# Syno_Ver1_0.net
KiCad netlist of a schematic drawn in EAGLE
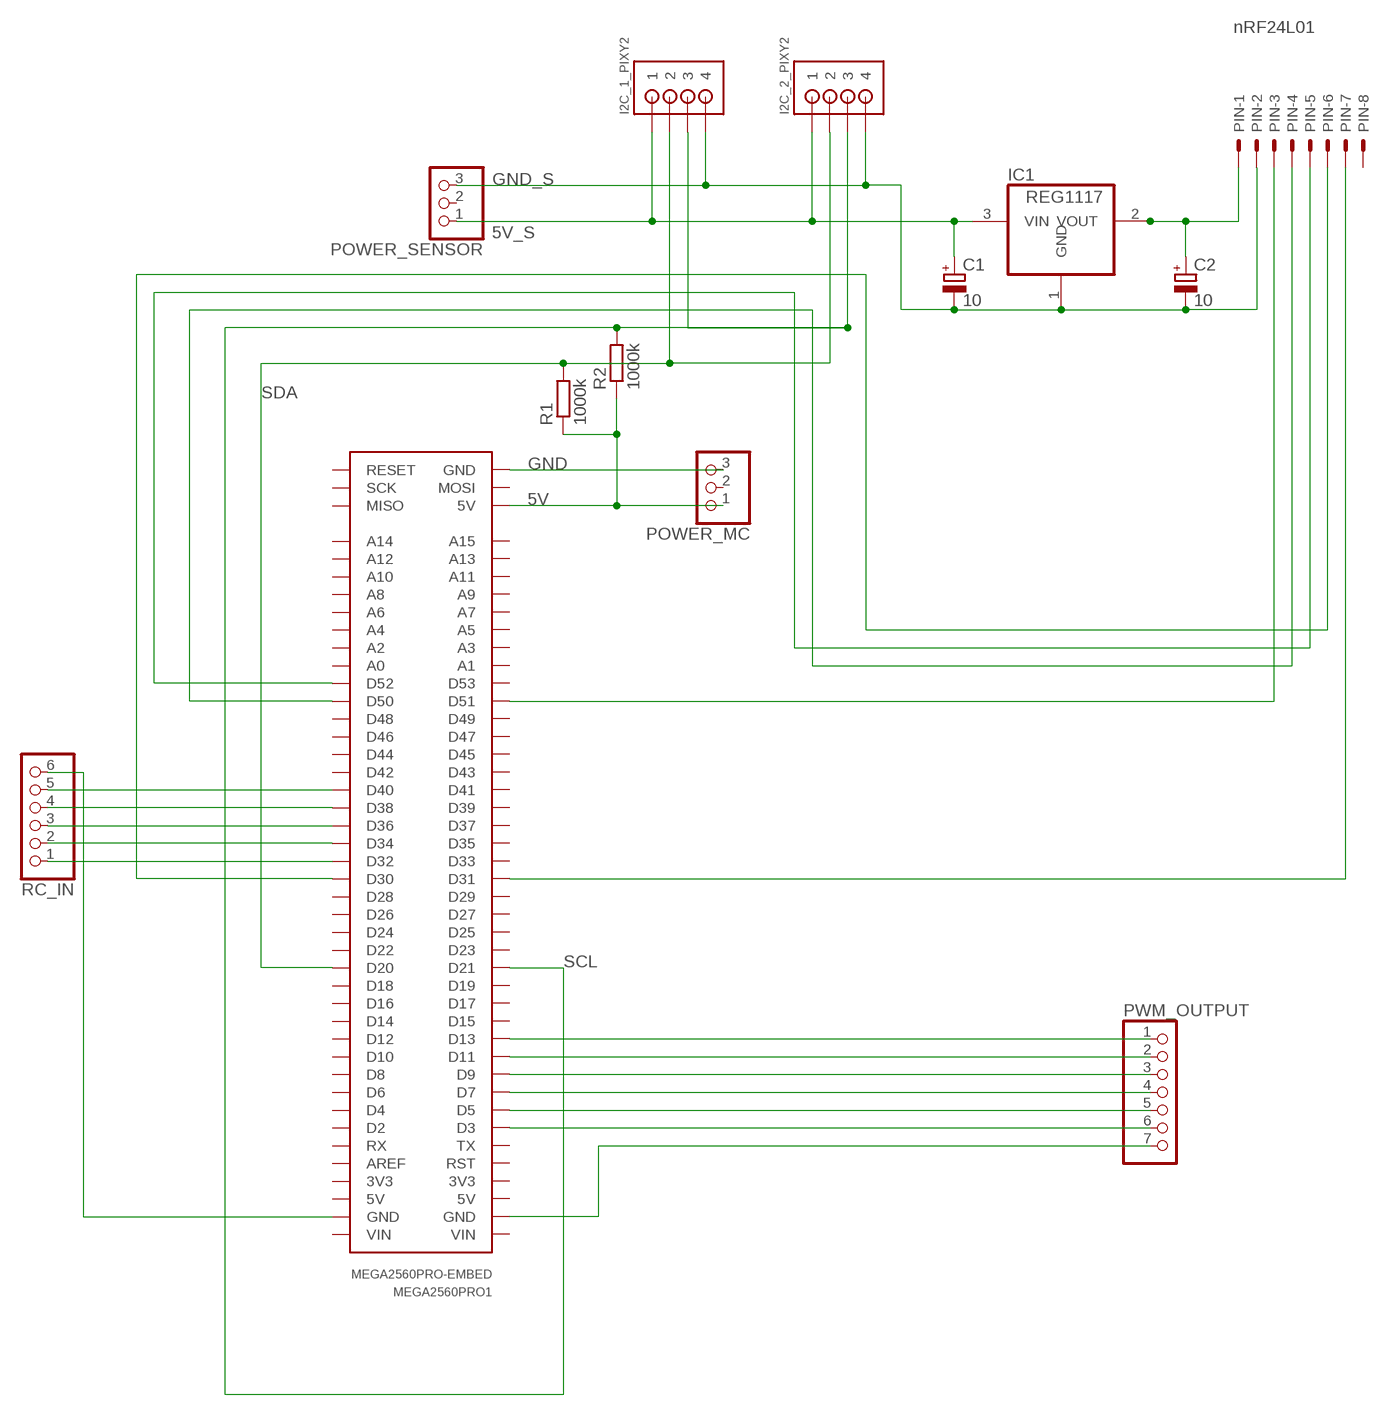
[diagram p0: schematic, sheet 1]

(export (version "E")
  (design (tool "Eeschema 10.0.6"))
  (components
    (comp (ref "C1")
      (value "10")
      (footprint "eagle-import:E1,8-4")
      (libsource (lib "eagle-import") (part "CPOL-EUE1.8-4"))
    )
    (comp (ref "C2")
      (value "10")
      (footprint "eagle-import:E1,8-4")
      (libsource (lib "eagle-import") (part "CPOL-EUE1.8-4"))
    )
    (comp (ref "I2C_1_PIXY2")
      (value "JST-PH_4-PIN_HEADER")
      (footprint "eagle-import:JST_B4B-PH_HEADER")
      (libsource (lib "eagle-import") (part "JST-PH_4-PIN_HEADER"))
    )
    (comp (ref "I2C_2_PIXY2")
      (value "JST-PH_4-PIN_HEADER")
      (footprint "eagle-import:JST_B4B-PH_HEADER")
      (libsource (lib "eagle-import") (part "JST-PH_4-PIN_HEADER"))
    )
    (comp (ref "IC1")
      (value "REG1117")
      (footprint "eagle-import:SOT223")
      (libsource (lib "eagle-import") (part "REG1117"))
    )
    (comp (ref "MEGA2560PRO1")
      (value "MEGA2560PRO-EMBED")
      (footprint "eagle-import:MEGA2560PRO-EMBED")
      (libsource (lib "eagle-import") (part "MEGA2560PRO-EMBED"))
    )
    (comp (ref "PIN")
      (value "nRF24L01")
      (footprint "eagle-import:JST-XH-08-PACKAGE-ROUND-PAD")
      (libsource (lib "eagle-import") (part "JST-XH-08-PIN-ROUND-PAD"))
    )
    (comp (ref "POWER_MC")
      (value "PINHD-1X3/90")
      (footprint "eagle-import:1X03_90")
      (libsource (lib "eagle-import") (part "PINHD-1X3/90"))
    )
    (comp (ref "POWER_SENSOR")
      (value "PINHD-1X3/90")
      (footprint "eagle-import:1X03_90")
      (libsource (lib "eagle-import") (part "PINHD-1X3/90"))
    )
    (comp (ref "PWM_OUTPUT")
      (value "PINHD-1X7/90")
      (footprint "eagle-import:1X07_90")
      (libsource (lib "eagle-import") (part "PINHD-1X7/90"))
    )
    (comp (ref "R1")
      (value "1000k")
      (footprint "eagle-import:0204_5")
      (libsource (lib "eagle-import") (part "R-EU_0204/5"))
    )
    (comp (ref "R2")
      (value "1000k")
      (footprint "eagle-import:0204_5")
      (libsource (lib "eagle-import") (part "R-EU_0204/5"))
    )
    (comp (ref "RC_IN")
      (value "PINHD-1X6/90")
      (footprint "eagle-import:1X06_90")
      (libsource (lib "eagle-import") (part "PINHD-1X6/90"))
    )
  )
  (nets
    (net (code "1") (name "/5V") (class "Default")
      (node (ref "MEGA2560PRO1") (pin "5V@3") (pinfunction "5V_5V@3") (pintype "bidirectional"))
      (node (ref "POWER_MC") (pin "1") (pinfunction "1_1") (pintype "passive"))
      (node (ref "R1") (pin "1") (pinfunction "1_1") (pintype "passive"))
      (node (ref "R2") (pin "1") (pinfunction "1_1") (pintype "passive"))
    )
    (net (code "2") (name "/5V_S") (class "Default")
      (node (ref "C1") (pin "+") (pinfunction "+_+") (pintype "passive"))
      (node (ref "I2C_1_PIXY2") (pin "P1") (pinfunction "1_P1") (pintype "bidirectional"))
      (node (ref "I2C_2_PIXY2") (pin "P1") (pinfunction "1_P1") (pintype "bidirectional"))
      (node (ref "IC1") (pin "3") (pinfunction "VIN_3") (pintype "input"))
      (node (ref "POWER_SENSOR") (pin "1") (pinfunction "1_1") (pintype "passive"))
    )
    (net (code "3") (name "/GND") (class "Default")
      (node (ref "MEGA2560PRO1") (pin "GND@3") (pinfunction "GND_GND@3") (pintype "bidirectional"))
      (node (ref "POWER_MC") (pin "3") (pinfunction "3_3") (pintype "passive"))
    )
    (net (code "4") (name "/GND_S") (class "Default")
      (node (ref "C1") (pin "-") (pinfunction "-_-") (pintype "passive"))
      (node (ref "C2") (pin "-") (pinfunction "-_-") (pintype "passive"))
      (node (ref "I2C_1_PIXY2") (pin "P4") (pinfunction "4_P4") (pintype "bidirectional"))
      (node (ref "I2C_2_PIXY2") (pin "P4") (pinfunction "4_P4") (pintype "bidirectional"))
      (node (ref "IC1") (pin "1") (pinfunction "GND_1") (pintype "power_in"))
      (node (ref "PIN") (pin "2") (pinfunction "S_2") (pintype "passive"))
      (node (ref "POWER_SENSOR") (pin "3") (pinfunction "3_3") (pintype "passive"))
    )
    (net (code "5") (name "/SCL") (class "Default")
      (node (ref "I2C_1_PIXY2") (pin "P3") (pinfunction "3_P3") (pintype "bidirectional"))
      (node (ref "I2C_2_PIXY2") (pin "P3") (pinfunction "3_P3") (pintype "bidirectional"))
      (node (ref "MEGA2560PRO1") (pin "D21") (pinfunction "D21_D21") (pintype "bidirectional"))
      (node (ref "R2") (pin "2") (pinfunction "2_2") (pintype "passive"))
    )
    (net (code "6") (name "/SDA") (class "Default")
      (node (ref "I2C_1_PIXY2") (pin "P2") (pinfunction "2_P2") (pintype "bidirectional"))
      (node (ref "I2C_2_PIXY2") (pin "P2") (pinfunction "2_P2") (pintype "bidirectional"))
      (node (ref "MEGA2560PRO1") (pin "D20") (pinfunction "D20_D20") (pintype "bidirectional"))
      (node (ref "R1") (pin "2") (pinfunction "2_2") (pintype "passive"))
    )
    (net (code "7") (name "Net-(IC1-VOUT)") (class "Default")
      (node (ref "C2") (pin "+") (pinfunction "+_+") (pintype "passive"))
      (node (ref "IC1") (pin "2") (pinfunction "VOUT_2") (pintype "output"))
      (node (ref "PIN") (pin "1") (pinfunction "S_1") (pintype "passive"))
    )
    (net (code "8") (name "Net-(MEGA2560PRO1-GND-PadGND@1)") (class "Default")
      (node (ref "MEGA2560PRO1") (pin "GND@1") (pinfunction "GND_GND@1") (pintype "bidirectional"))
      (node (ref "PWM_OUTPUT") (pin "7") (pinfunction "7_7") (pintype "passive"))
    )
    (net (code "9") (name "Net-(MEGA2560PRO1-GND-PadGND@2)") (class "Default")
      (node (ref "MEGA2560PRO1") (pin "GND@2") (pinfunction "GND_GND@2") (pintype "bidirectional"))
      (node (ref "RC_IN") (pin "6") (pinfunction "6_6") (pintype "passive"))
    )
    (net (code "10") (name "Net-(MEGA2560PRO1-PadD3)") (class "Default")
      (node (ref "MEGA2560PRO1") (pin "D3") (pinfunction "D3_D3") (pintype "bidirectional"))
      (node (ref "PWM_OUTPUT") (pin "6") (pinfunction "6_6") (pintype "passive"))
    )
    (net (code "11") (name "Net-(MEGA2560PRO1-PadD5)") (class "Default")
      (node (ref "MEGA2560PRO1") (pin "D5") (pinfunction "D5_D5") (pintype "bidirectional"))
      (node (ref "PWM_OUTPUT") (pin "5") (pinfunction "5_5") (pintype "passive"))
    )
    (net (code "12") (name "Net-(MEGA2560PRO1-PadD7)") (class "Default")
      (node (ref "MEGA2560PRO1") (pin "D7") (pinfunction "D7_D7") (pintype "bidirectional"))
      (node (ref "PWM_OUTPUT") (pin "4") (pinfunction "4_4") (pintype "passive"))
    )
    (net (code "13") (name "Net-(MEGA2560PRO1-PadD9)") (class "Default")
      (node (ref "MEGA2560PRO1") (pin "D9") (pinfunction "D9_D9") (pintype "bidirectional"))
      (node (ref "PWM_OUTPUT") (pin "3") (pinfunction "3_3") (pintype "passive"))
    )
    (net (code "14") (name "Net-(MEGA2560PRO1-PadD11)") (class "Default")
      (node (ref "MEGA2560PRO1") (pin "D11") (pinfunction "D11_D11") (pintype "bidirectional"))
      (node (ref "PWM_OUTPUT") (pin "2") (pinfunction "2_2") (pintype "passive"))
    )
    (net (code "15") (name "Net-(MEGA2560PRO1-PadD13)") (class "Default")
      (node (ref "MEGA2560PRO1") (pin "D13") (pinfunction "D13_D13") (pintype "bidirectional"))
      (node (ref "PWM_OUTPUT") (pin "1") (pinfunction "1_1") (pintype "passive"))
    )
    (net (code "16") (name "Net-(MEGA2560PRO1-PadD32)") (class "Default")
      (node (ref "MEGA2560PRO1") (pin "D32") (pinfunction "D32_D32") (pintype "bidirectional"))
      (node (ref "RC_IN") (pin "1") (pinfunction "1_1") (pintype "passive"))
    )
    (net (code "17") (name "Net-(MEGA2560PRO1-PadD34)") (class "Default")
      (node (ref "MEGA2560PRO1") (pin "D34") (pinfunction "D34_D34") (pintype "bidirectional"))
      (node (ref "RC_IN") (pin "2") (pinfunction "2_2") (pintype "passive"))
    )
    (net (code "18") (name "Net-(MEGA2560PRO1-PadD36)") (class "Default")
      (node (ref "MEGA2560PRO1") (pin "D36") (pinfunction "D36_D36") (pintype "bidirectional"))
      (node (ref "RC_IN") (pin "3") (pinfunction "3_3") (pintype "passive"))
    )
    (net (code "19") (name "Net-(MEGA2560PRO1-PadD38)") (class "Default")
      (node (ref "MEGA2560PRO1") (pin "D38") (pinfunction "D38_D38") (pintype "bidirectional"))
      (node (ref "RC_IN") (pin "4") (pinfunction "4_4") (pintype "passive"))
    )
    (net (code "20") (name "Net-(MEGA2560PRO1-PadD40)") (class "Default")
      (node (ref "MEGA2560PRO1") (pin "D40") (pinfunction "D40_D40") (pintype "bidirectional"))
      (node (ref "RC_IN") (pin "5") (pinfunction "5_5") (pintype "passive"))
    )
    (net (code "21") (name "Net-(PINC-S)") (class "Default")
      (node (ref "MEGA2560PRO1") (pin "D51") (pinfunction "D51_D51") (pintype "bidirectional"))
      (node (ref "PIN") (pin "3") (pinfunction "S_3") (pintype "passive"))
    )
    (net (code "22") (name "Net-(PIND-S)") (class "Default")
      (node (ref "MEGA2560PRO1") (pin "D50") (pinfunction "D50_D50") (pintype "bidirectional"))
      (node (ref "PIN") (pin "4") (pinfunction "S_4") (pintype "passive"))
    )
    (net (code "23") (name "Net-(PINE-S)") (class "Default")
      (node (ref "MEGA2560PRO1") (pin "D52") (pinfunction "D52_D52") (pintype "bidirectional"))
      (node (ref "PIN") (pin "5") (pinfunction "S_5") (pintype "passive"))
    )
    (net (code "24") (name "Net-(PINF-S)") (class "Default")
      (node (ref "MEGA2560PRO1") (pin "D30") (pinfunction "D30_D30") (pintype "bidirectional"))
      (node (ref "PIN") (pin "6") (pinfunction "S_6") (pintype "passive"))
    )
    (net (code "25") (name "Net-(PING-S)") (class "Default")
      (node (ref "MEGA2560PRO1") (pin "D31") (pinfunction "D31_D31") (pintype "bidirectional"))
      (node (ref "PIN") (pin "7") (pinfunction "S_7") (pintype "passive"))
    )
    (net (code "26") (name "unconnected-(MEGA2560PRO1-3V3-Pad3V3@1)") (class "Default")
      (node (ref "MEGA2560PRO1") (pin "3V3@1") (pinfunction "3V3_3V3@1") (pintype "bidirectional"))
    )
    (net (code "27") (name "unconnected-(MEGA2560PRO1-3V3-Pad3V3@2)") (class "Default")
      (node (ref "MEGA2560PRO1") (pin "3V3@2") (pinfunction "3V3_3V3@2") (pintype "bidirectional"))
    )
    (net (code "28") (name "unconnected-(MEGA2560PRO1-5V-Pad5V@1)") (class "Default")
      (node (ref "MEGA2560PRO1") (pin "5V@1") (pinfunction "5V_5V@1") (pintype "bidirectional"))
    )
    (net (code "29") (name "unconnected-(MEGA2560PRO1-5V-Pad5V@2)") (class "Default")
      (node (ref "MEGA2560PRO1") (pin "5V@2") (pinfunction "5V_5V@2") (pintype "bidirectional"))
    )
    (net (code "30") (name "unconnected-(MEGA2560PRO1-PadA0)") (class "Default")
      (node (ref "MEGA2560PRO1") (pin "A0") (pinfunction "A0_A0") (pintype "bidirectional"))
    )
    (net (code "31") (name "unconnected-(MEGA2560PRO1-PadA1)") (class "Default")
      (node (ref "MEGA2560PRO1") (pin "A1") (pinfunction "A1_A1") (pintype "bidirectional"))
    )
    (net (code "32") (name "unconnected-(MEGA2560PRO1-PadA2)") (class "Default")
      (node (ref "MEGA2560PRO1") (pin "A2") (pinfunction "A2_A2") (pintype "bidirectional"))
    )
    (net (code "33") (name "unconnected-(MEGA2560PRO1-PadA3)") (class "Default")
      (node (ref "MEGA2560PRO1") (pin "A3") (pinfunction "A3_A3") (pintype "bidirectional"))
    )
    (net (code "34") (name "unconnected-(MEGA2560PRO1-PadA4)") (class "Default")
      (node (ref "MEGA2560PRO1") (pin "A4") (pinfunction "A4_A4") (pintype "bidirectional"))
    )
    (net (code "35") (name "unconnected-(MEGA2560PRO1-PadA5)") (class "Default")
      (node (ref "MEGA2560PRO1") (pin "A5") (pinfunction "A5_A5") (pintype "bidirectional"))
    )
    (net (code "36") (name "unconnected-(MEGA2560PRO1-PadA6)") (class "Default")
      (node (ref "MEGA2560PRO1") (pin "A6") (pinfunction "A6_A6") (pintype "bidirectional"))
    )
    (net (code "37") (name "unconnected-(MEGA2560PRO1-PadA7)") (class "Default")
      (node (ref "MEGA2560PRO1") (pin "A7") (pinfunction "A7_A7") (pintype "bidirectional"))
    )
    (net (code "38") (name "unconnected-(MEGA2560PRO1-PadA8)") (class "Default")
      (node (ref "MEGA2560PRO1") (pin "A8") (pinfunction "A8_A8") (pintype "bidirectional"))
    )
    (net (code "39") (name "unconnected-(MEGA2560PRO1-PadA9)") (class "Default")
      (node (ref "MEGA2560PRO1") (pin "A9") (pinfunction "A9_A9") (pintype "bidirectional"))
    )
    (net (code "40") (name "unconnected-(MEGA2560PRO1-PadA10)") (class "Default")
      (node (ref "MEGA2560PRO1") (pin "A10") (pinfunction "A10_A10") (pintype "bidirectional"))
    )
    (net (code "41") (name "unconnected-(MEGA2560PRO1-PadA11)") (class "Default")
      (node (ref "MEGA2560PRO1") (pin "A11") (pinfunction "A11_A11") (pintype "bidirectional"))
    )
    (net (code "42") (name "unconnected-(MEGA2560PRO1-PadA12)") (class "Default")
      (node (ref "MEGA2560PRO1") (pin "A12") (pinfunction "A12_A12") (pintype "bidirectional"))
    )
    (net (code "43") (name "unconnected-(MEGA2560PRO1-PadA13)") (class "Default")
      (node (ref "MEGA2560PRO1") (pin "A13") (pinfunction "A13_A13") (pintype "bidirectional"))
    )
    (net (code "44") (name "unconnected-(MEGA2560PRO1-PadA14)") (class "Default")
      (node (ref "MEGA2560PRO1") (pin "A14") (pinfunction "A14_A14") (pintype "bidirectional"))
    )
    (net (code "45") (name "unconnected-(MEGA2560PRO1-PadA15)") (class "Default")
      (node (ref "MEGA2560PRO1") (pin "A15") (pinfunction "A15_A15") (pintype "bidirectional"))
    )
    (net (code "46") (name "unconnected-(MEGA2560PRO1-PadAREF)") (class "Default")
      (node (ref "MEGA2560PRO1") (pin "AREF") (pinfunction "AREF_AREF") (pintype "bidirectional"))
    )
    (net (code "47") (name "unconnected-(MEGA2560PRO1-PadD2)") (class "Default")
      (node (ref "MEGA2560PRO1") (pin "D2") (pinfunction "D2_D2") (pintype "bidirectional"))
    )
    (net (code "48") (name "unconnected-(MEGA2560PRO1-PadD4)") (class "Default")
      (node (ref "MEGA2560PRO1") (pin "D4") (pinfunction "D4_D4") (pintype "bidirectional"))
    )
    (net (code "49") (name "unconnected-(MEGA2560PRO1-PadD6)") (class "Default")
      (node (ref "MEGA2560PRO1") (pin "D6") (pinfunction "D6_D6") (pintype "bidirectional"))
    )
    (net (code "50") (name "unconnected-(MEGA2560PRO1-PadD8)") (class "Default")
      (node (ref "MEGA2560PRO1") (pin "D8") (pinfunction "D8_D8") (pintype "bidirectional"))
    )
    (net (code "51") (name "unconnected-(MEGA2560PRO1-PadD10)") (class "Default")
      (node (ref "MEGA2560PRO1") (pin "D10") (pinfunction "D10_D10") (pintype "bidirectional"))
    )
    (net (code "52") (name "unconnected-(MEGA2560PRO1-PadD12)") (class "Default")
      (node (ref "MEGA2560PRO1") (pin "D12") (pinfunction "D12_D12") (pintype "bidirectional"))
    )
    (net (code "53") (name "unconnected-(MEGA2560PRO1-PadD14)") (class "Default")
      (node (ref "MEGA2560PRO1") (pin "D14") (pinfunction "D14_D14") (pintype "bidirectional"))
    )
    (net (code "54") (name "unconnected-(MEGA2560PRO1-PadD15)") (class "Default")
      (node (ref "MEGA2560PRO1") (pin "D15") (pinfunction "D15_D15") (pintype "bidirectional"))
    )
    (net (code "55") (name "unconnected-(MEGA2560PRO1-PadD16)") (class "Default")
      (node (ref "MEGA2560PRO1") (pin "D16") (pinfunction "D16_D16") (pintype "bidirectional"))
    )
    (net (code "56") (name "unconnected-(MEGA2560PRO1-PadD17)") (class "Default")
      (node (ref "MEGA2560PRO1") (pin "D17") (pinfunction "D17_D17") (pintype "bidirectional"))
    )
    (net (code "57") (name "unconnected-(MEGA2560PRO1-PadD18)") (class "Default")
      (node (ref "MEGA2560PRO1") (pin "D18") (pinfunction "D18_D18") (pintype "bidirectional"))
    )
    (net (code "58") (name "unconnected-(MEGA2560PRO1-PadD19)") (class "Default")
      (node (ref "MEGA2560PRO1") (pin "D19") (pinfunction "D19_D19") (pintype "bidirectional"))
    )
    (net (code "59") (name "unconnected-(MEGA2560PRO1-PadD22)") (class "Default")
      (node (ref "MEGA2560PRO1") (pin "D22") (pinfunction "D22_D22") (pintype "bidirectional"))
    )
    (net (code "60") (name "unconnected-(MEGA2560PRO1-PadD23)") (class "Default")
      (node (ref "MEGA2560PRO1") (pin "D23") (pinfunction "D23_D23") (pintype "bidirectional"))
    )
    (net (code "61") (name "unconnected-(MEGA2560PRO1-PadD24)") (class "Default")
      (node (ref "MEGA2560PRO1") (pin "D24") (pinfunction "D24_D24") (pintype "bidirectional"))
    )
    (net (code "62") (name "unconnected-(MEGA2560PRO1-PadD25)") (class "Default")
      (node (ref "MEGA2560PRO1") (pin "D25") (pinfunction "D25_D25") (pintype "bidirectional"))
    )
    (net (code "63") (name "unconnected-(MEGA2560PRO1-PadD26)") (class "Default")
      (node (ref "MEGA2560PRO1") (pin "D26") (pinfunction "D26_D26") (pintype "bidirectional"))
    )
    (net (code "64") (name "unconnected-(MEGA2560PRO1-PadD27)") (class "Default")
      (node (ref "MEGA2560PRO1") (pin "D27") (pinfunction "D27_D27") (pintype "bidirectional"))
    )
    (net (code "65") (name "unconnected-(MEGA2560PRO1-PadD28)") (class "Default")
      (node (ref "MEGA2560PRO1") (pin "D28") (pinfunction "D28_D28") (pintype "bidirectional"))
    )
    (net (code "66") (name "unconnected-(MEGA2560PRO1-PadD29)") (class "Default")
      (node (ref "MEGA2560PRO1") (pin "D29") (pinfunction "D29_D29") (pintype "bidirectional"))
    )
    (net (code "67") (name "unconnected-(MEGA2560PRO1-PadD33)") (class "Default")
      (node (ref "MEGA2560PRO1") (pin "D33") (pinfunction "D33_D33") (pintype "bidirectional"))
    )
    (net (code "68") (name "unconnected-(MEGA2560PRO1-PadD35)") (class "Default")
      (node (ref "MEGA2560PRO1") (pin "D35") (pinfunction "D35_D35") (pintype "bidirectional"))
    )
    (net (code "69") (name "unconnected-(MEGA2560PRO1-PadD37)") (class "Default")
      (node (ref "MEGA2560PRO1") (pin "D37") (pinfunction "D37_D37") (pintype "bidirectional"))
    )
    (net (code "70") (name "unconnected-(MEGA2560PRO1-PadD39)") (class "Default")
      (node (ref "MEGA2560PRO1") (pin "D39") (pinfunction "D39_D39") (pintype "bidirectional"))
    )
    (net (code "71") (name "unconnected-(MEGA2560PRO1-PadD41)") (class "Default")
      (node (ref "MEGA2560PRO1") (pin "D41") (pinfunction "D41_D41") (pintype "bidirectional"))
    )
    (net (code "72") (name "unconnected-(MEGA2560PRO1-PadD42)") (class "Default")
      (node (ref "MEGA2560PRO1") (pin "D42") (pinfunction "D42_D42") (pintype "bidirectional"))
    )
    (net (code "73") (name "unconnected-(MEGA2560PRO1-PadD43)") (class "Default")
      (node (ref "MEGA2560PRO1") (pin "D43") (pinfunction "D43_D43") (pintype "bidirectional"))
    )
    (net (code "74") (name "unconnected-(MEGA2560PRO1-PadD44)") (class "Default")
      (node (ref "MEGA2560PRO1") (pin "D44") (pinfunction "D44_D44") (pintype "bidirectional"))
    )
    (net (code "75") (name "unconnected-(MEGA2560PRO1-PadD45)") (class "Default")
      (node (ref "MEGA2560PRO1") (pin "D45") (pinfunction "D45_D45") (pintype "bidirectional"))
    )
    (net (code "76") (name "unconnected-(MEGA2560PRO1-PadD46)") (class "Default")
      (node (ref "MEGA2560PRO1") (pin "D46") (pinfunction "D46_D46") (pintype "bidirectional"))
    )
    (net (code "77") (name "unconnected-(MEGA2560PRO1-PadD47)") (class "Default")
      (node (ref "MEGA2560PRO1") (pin "D47") (pinfunction "D47_D47") (pintype "bidirectional"))
    )
    (net (code "78") (name "unconnected-(MEGA2560PRO1-PadD48)") (class "Default")
      (node (ref "MEGA2560PRO1") (pin "D48") (pinfunction "D48_D48") (pintype "bidirectional"))
    )
    (net (code "79") (name "unconnected-(MEGA2560PRO1-PadD49)") (class "Default")
      (node (ref "MEGA2560PRO1") (pin "D49") (pinfunction "D49_D49") (pintype "bidirectional"))
    )
    (net (code "80") (name "unconnected-(MEGA2560PRO1-PadD53)") (class "Default")
      (node (ref "MEGA2560PRO1") (pin "D53") (pinfunction "D53_D53") (pintype "bidirectional"))
    )
    (net (code "81") (name "unconnected-(MEGA2560PRO1-PadMISO)") (class "Default")
      (node (ref "MEGA2560PRO1") (pin "MISO") (pinfunction "MISO_MISO") (pintype "bidirectional"))
    )
    (net (code "82") (name "unconnected-(MEGA2560PRO1-PadMOSI)") (class "Default")
      (node (ref "MEGA2560PRO1") (pin "MOSI") (pinfunction "MOSI_MOSI") (pintype "bidirectional"))
    )
    (net (code "83") (name "unconnected-(MEGA2560PRO1-PadRESET)") (class "Default")
      (node (ref "MEGA2560PRO1") (pin "RESET") (pinfunction "RESET_RESET") (pintype "bidirectional"))
    )
    (net (code "84") (name "unconnected-(MEGA2560PRO1-PadRST)") (class "Default")
      (node (ref "MEGA2560PRO1") (pin "RST") (pinfunction "RST_RST") (pintype "bidirectional"))
    )
    (net (code "85") (name "unconnected-(MEGA2560PRO1-PadRX)") (class "Default")
      (node (ref "MEGA2560PRO1") (pin "RX") (pinfunction "RX_RX") (pintype "bidirectional"))
    )
    (net (code "86") (name "unconnected-(MEGA2560PRO1-PadSCK)") (class "Default")
      (node (ref "MEGA2560PRO1") (pin "SCK") (pinfunction "SCK_SCK") (pintype "bidirectional"))
    )
    (net (code "87") (name "unconnected-(MEGA2560PRO1-PadTX)") (class "Default")
      (node (ref "MEGA2560PRO1") (pin "TX") (pinfunction "TX_TX") (pintype "bidirectional"))
    )
    (net (code "88") (name "unconnected-(MEGA2560PRO1-VIN-PadVIN@1)") (class "Default")
      (node (ref "MEGA2560PRO1") (pin "VIN@1") (pinfunction "VIN_VIN@1") (pintype "bidirectional"))
    )
    (net (code "89") (name "unconnected-(MEGA2560PRO1-VIN-PadVIN@2)") (class "Default")
      (node (ref "MEGA2560PRO1") (pin "VIN@2") (pinfunction "VIN_VIN@2") (pintype "bidirectional"))
    )
    (net (code "90") (name "unconnected-(PINH-S-Pad8)") (class "Default")
      (node (ref "PIN") (pin "8") (pinfunction "S_8") (pintype "passive"))
    )
    (net (code "91") (name "unconnected-(POWER_MC-Pad2)") (class "Default")
      (node (ref "POWER_MC") (pin "2") (pinfunction "2_2") (pintype "passive"))
    )
    (net (code "92") (name "unconnected-(POWER_SENSOR-Pad2)") (class "Default")
      (node (ref "POWER_SENSOR") (pin "2") (pinfunction "2_2") (pintype "passive"))
    )
  )
)
